# 26__schdoc.net
KiCad netlist of a schematic drawn in Altium Designer
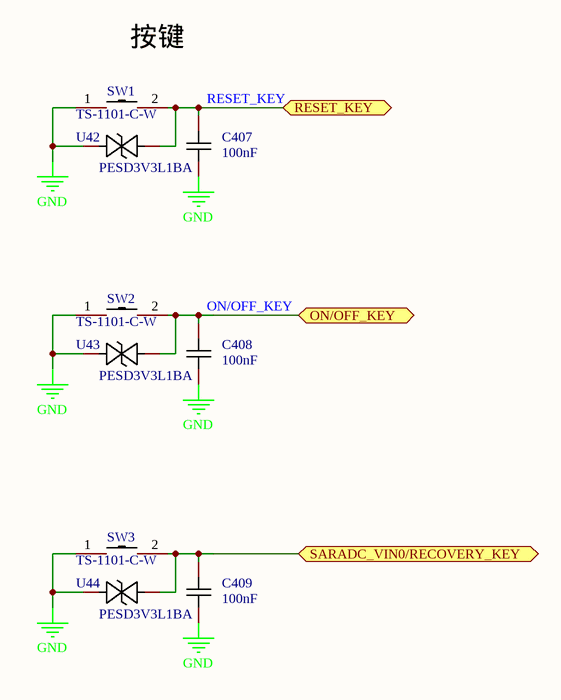
[diagram p0: 26_按键接口.schdoc.schdoc]

(export (version "E")
  (design (tool "Eeschema 10.0.6"))
  (components
    (comp (ref "C407")
      (value "100nF")
      (footprint "C0603")
      (fields
        (field (name "NAME") "100nF")
        (field (name "MANUFACTURER") "YAGEO(国巨)")
        (field (name "MANUFACTURER PART") "CC0603KRX7R9BB104")
        (field (name "TOLERANCE") "±10%")
      )
      (libsource (lib "altium-import") (part "root_1_CC0603KRX7R9BB104_"))
    )
    (comp (ref "C408")
      (value "100nF")
      (footprint "C0603")
      (fields
        (field (name "NAME") "100nF")
        (field (name "MANUFACTURER") "YAGEO(国巨)")
        (field (name "MANUFACTURER PART") "CC0603KRX7R9BB104")
        (field (name "TOLERANCE") "±10%")
      )
      (libsource (lib "altium-import") (part "root_1_CC0603KRX7R9BB104_"))
    )
    (comp (ref "C409")
      (value "100nF")
      (footprint "C0603")
      (fields
        (field (name "NAME") "100nF")
        (field (name "MANUFACTURER") "YAGEO(国巨)")
        (field (name "MANUFACTURER PART") "CC0603KRX7R9BB104")
        (field (name "TOLERANCE") "±10%")
      )
      (libsource (lib "altium-import") (part "root_1_CC0603KRX7R9BB104_"))
    )
    (comp (ref "SW1")
      (value "TS-1101-C-W")
      (footprint "SW-SMD_L6.0-W3.3-LS8.0")
      (fields (field (name "NAME") "TS-1101-C-W") (field (name "MANUFACTURER") "XKB Connectivity(中国星坤)"))
      (libsource (lib "altium-import") (part "root_0_TS-1101-C-W_"))
    )
    (comp (ref "SW2")
      (value "TS-1101-C-W")
      (footprint "SW-SMD_L6.0-W3.3-LS8.0")
      (fields (field (name "NAME") "TS-1101-C-W") (field (name "MANUFACTURER") "XKB Connectivity(中国星坤)"))
      (libsource (lib "altium-import") (part "root_0_TS-1101-C-W_"))
    )
    (comp (ref "SW3")
      (value "TS-1101-C-W")
      (footprint "SW-SMD_L6.0-W3.3-LS8.0")
      (fields (field (name "NAME") "TS-1101-C-W") (field (name "MANUFACTURER") "XKB Connectivity(中国星坤)"))
      (libsource (lib "altium-import") (part "root_0_TS-1101-C-W_"))
    )
    (comp (ref "U42")
      (value "PESD3V3L1BA")
      (footprint "SOD-323_L1.7-W1.3-LS2.6-BI")
      (fields (field (name "NAME") "PESD3V3L1BA") (field (name "MANUFACTURER") "UMW(友台半导体)"))
      (libsource (lib "altium-import") (part "root_0_PESD3V3L1BA_C2687129_"))
    )
    (comp (ref "U43")
      (value "PESD3V3L1BA")
      (footprint "SOD-323_L1.7-W1.3-LS2.6-BI")
      (fields (field (name "NAME") "PESD3V3L1BA") (field (name "MANUFACTURER") "UMW(友台半导体)"))
      (libsource (lib "altium-import") (part "root_0_PESD3V3L1BA_C2687129_"))
    )
    (comp (ref "U44")
      (value "PESD3V3L1BA")
      (footprint "SOD-323_L1.7-W1.3-LS2.6-BI")
      (fields (field (name "NAME") "PESD3V3L1BA") (field (name "MANUFACTURER") "UMW(友台半导体)"))
      (libsource (lib "altium-import") (part "root_0_PESD3V3L1BA_C2687129_"))
    )
  )
  (nets
    (net (code "1") (name "/ON{slash}OFF_KEY") (class "Default")
      (node (ref "C408") (pin "2") (pinfunction "2_2") (pintype "passive"))
      (node (ref "SW2") (pin "2") (pinfunction "2_2") (pintype "passive"))
      (node (ref "U43") (pin "2") (pinfunction "2_2") (pintype "passive"))
    )
    (net (code "2") (name "/RESET_KEY") (class "Default")
      (node (ref "C407") (pin "2") (pinfunction "2_2") (pintype "passive"))
      (node (ref "SW1") (pin "2") (pinfunction "2_2") (pintype "passive"))
      (node (ref "U42") (pin "2") (pinfunction "2_2") (pintype "passive"))
    )
    (net (code "3") (name "/SARADC_VIN0{slash}RECOVERY_KEY") (class "Default")
      (node (ref "C409") (pin "2") (pinfunction "2_2") (pintype "passive"))
      (node (ref "SW3") (pin "2") (pinfunction "2_2") (pintype "passive"))
      (node (ref "U44") (pin "2") (pinfunction "2_2") (pintype "passive"))
    )
    (net (code "4") (name "GND") (class "Default")
      (node (ref "C407") (pin "1") (pinfunction "1_1") (pintype "passive"))
      (node (ref "C408") (pin "1") (pinfunction "1_1") (pintype "passive"))
      (node (ref "C409") (pin "1") (pinfunction "1_1") (pintype "passive"))
      (node (ref "SW1") (pin "1") (pinfunction "1_1") (pintype "passive"))
      (node (ref "SW2") (pin "1") (pinfunction "1_1") (pintype "passive"))
      (node (ref "SW3") (pin "1") (pinfunction "1_1") (pintype "passive"))
      (node (ref "U42") (pin "1") (pinfunction "1_1") (pintype "passive"))
      (node (ref "U43") (pin "1") (pinfunction "1_1") (pintype "passive"))
      (node (ref "U44") (pin "1") (pinfunction "1_1") (pintype "passive"))
    )
  )
)
